# Power_USB.net
KiCad netlist of a schematic drawn in Altium Designer
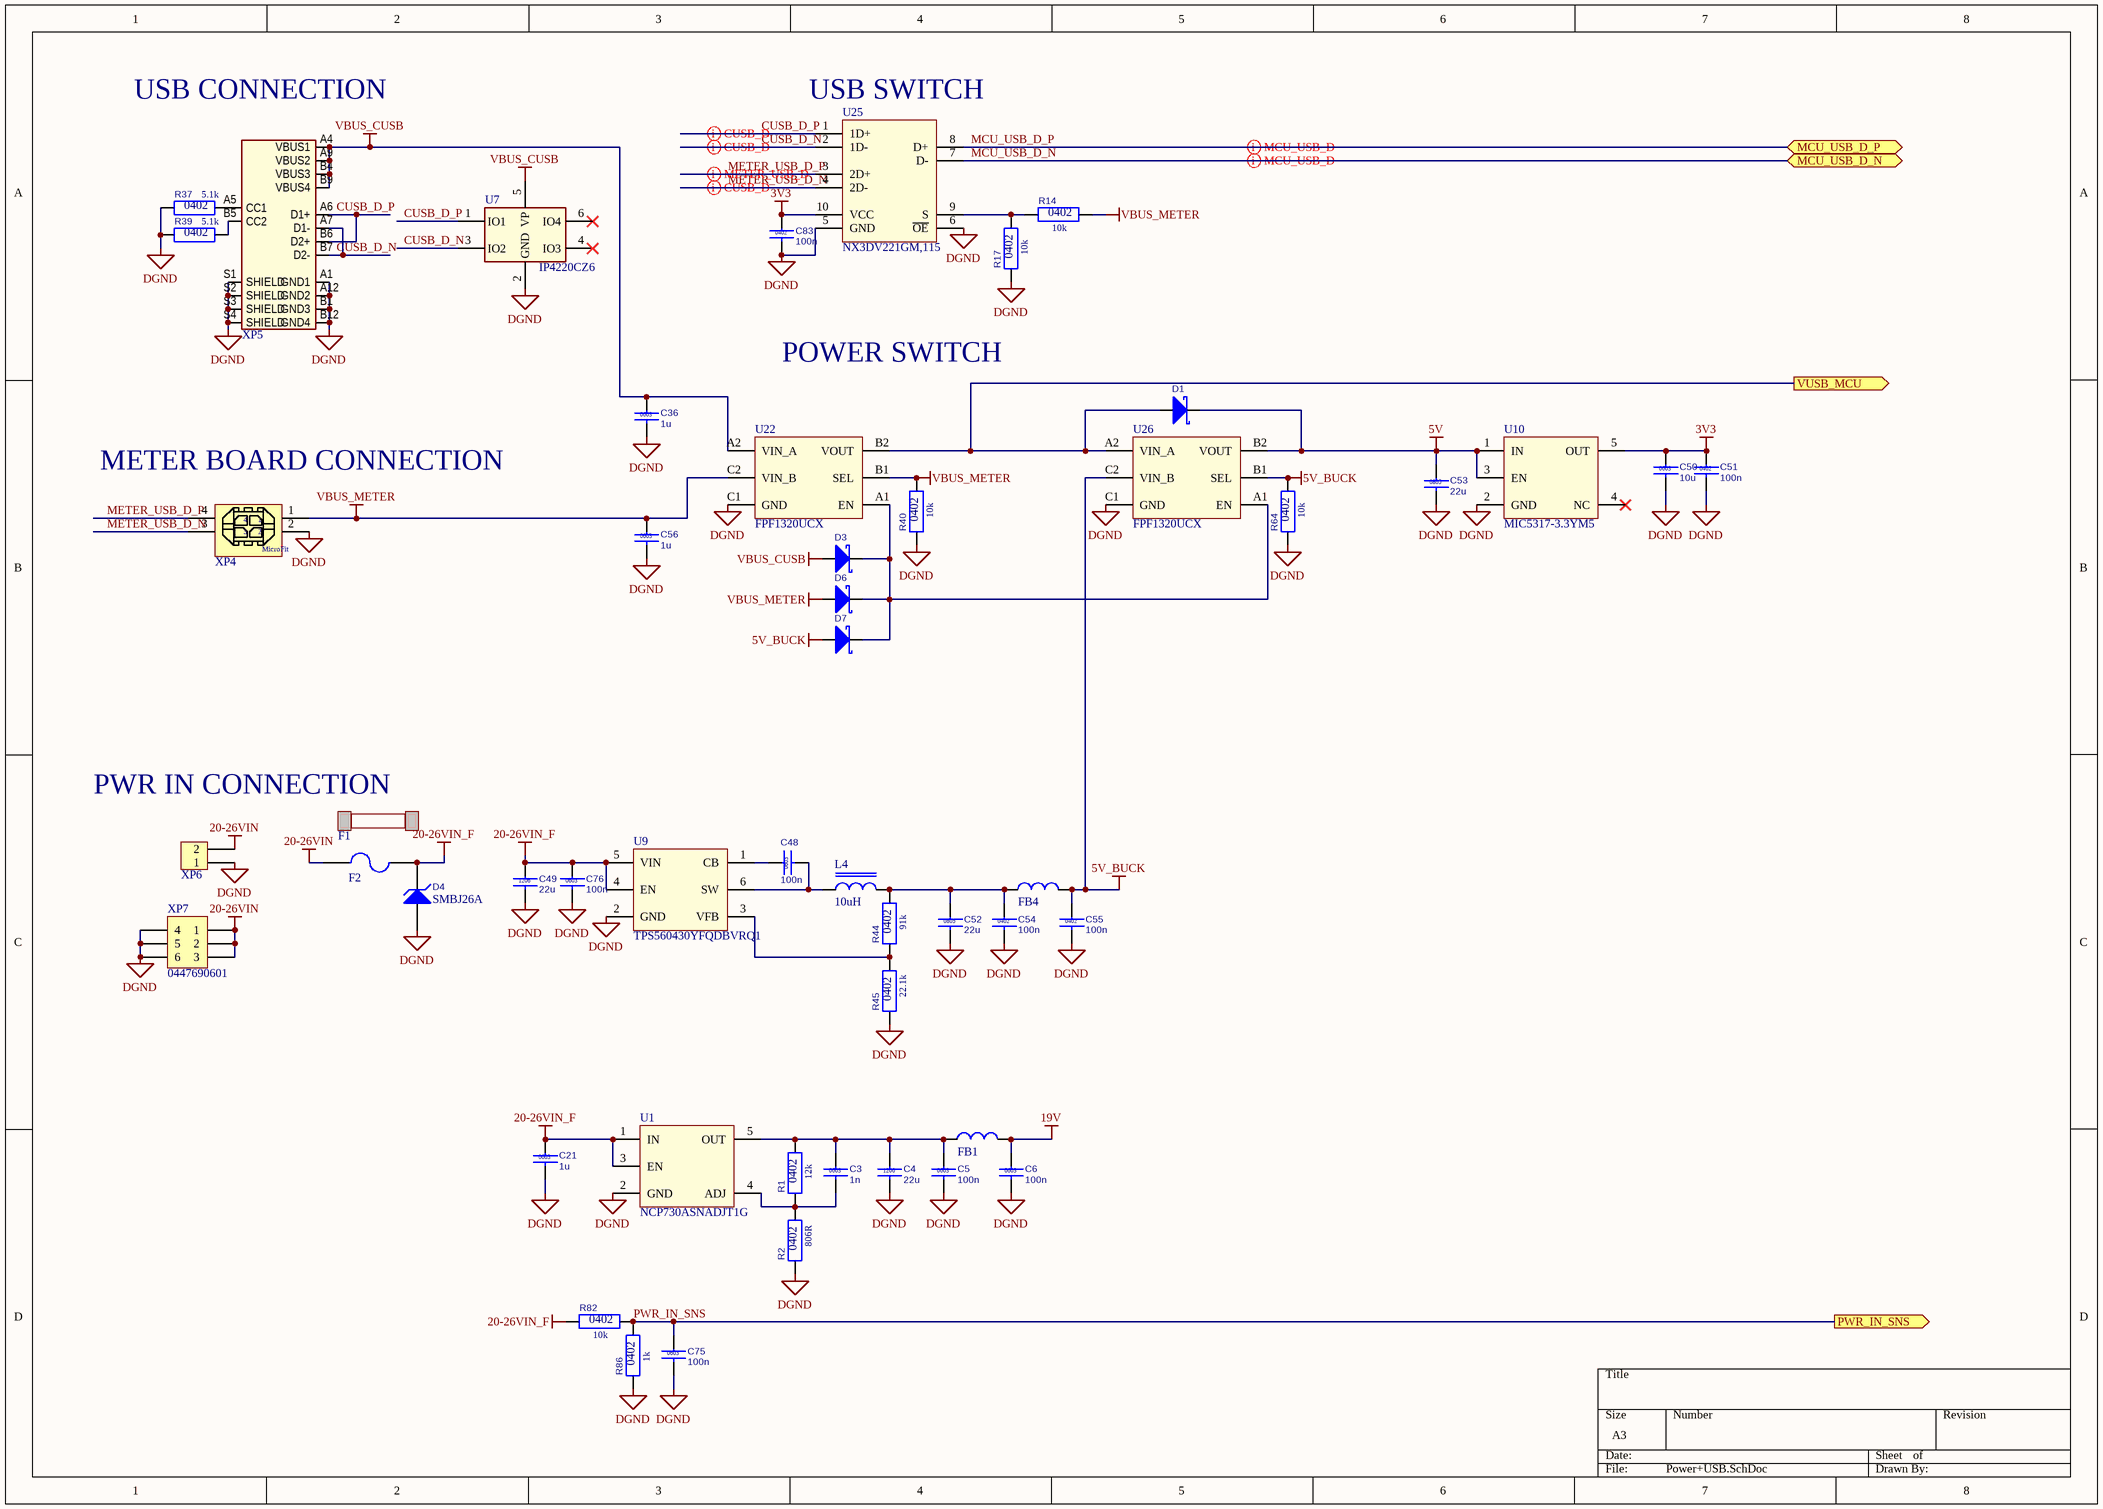
[diagram p0: Power+USB.SchDoc]

(export (version "E")
  (design (tool "Eeschema 10.0.6"))
  (components
    (comp (ref "C3")
      (value "1n")
      (footprint "CC0603M")
      (description "Chip ceramic capacitor")
      (fields
        (field (name "CASE") "0603")
        (field (name "PARTNUMBER") "CC0603K-X7R-50V-1N-M")
        (field (name "MANUFACTURER") "Yageo")
        (field (name "PUBLISHER") "alexey.savchenko")
      )
      (libsource (lib "AltiumLib") (part "Capacitor_nonpolar"))
    )
    (comp (ref "C4")
      (value "22u")
      (footprint "CC1206M")
      (description "Chip ceramic capacitor")
      (fields
        (field (name "CASE") "1206")
        (field (name "PARTNUMBER") "CC1206K-X5R-35V-22U-M")
        (field (name "MANUFACTURER") "TDK")
        (field (name "PUBLISHER") "alexey.savchenko")
      )
      (libsource (lib "AltiumLib") (part "Capacitor_nonpolar"))
    )
    (comp (ref "C5")
      (value "100n")
      (footprint "CC0603M")
      (description "Chip ceramic capacitor")
      (fields
        (field (name "CASE") "0603")
        (field (name "PARTNUMBER") "CC0603K-X7R-50V-100N-M")
        (field (name "MANUFACTURER") "Yageo")
        (field (name "PUBLISHER") "alexey.savchenko")
      )
      (libsource (lib "AltiumLib") (part "Capacitor_nonpolar"))
    )
    (comp (ref "C6")
      (value "100n")
      (footprint "CC0603M")
      (description "Chip ceramic capacitor")
      (fields
        (field (name "CASE") "0603")
        (field (name "PARTNUMBER") "CC0603K-X7R-50V-100N-M")
        (field (name "MANUFACTURER") "Yageo")
        (field (name "PUBLISHER") "alexey.savchenko")
      )
      (libsource (lib "AltiumLib") (part "Capacitor_nonpolar"))
    )
    (comp (ref "C21")
      (value "1u")
      (footprint "CC0603M")
      (description "Chip ceramic capacitor")
      (fields
        (field (name "CASE") "0603")
        (field (name "PARTNUMBER") "CC0603K-X5R-50V-1U-M")
        (field (name "MANUFACTURER") "Samsung")
        (field (name "PUBLISHER") "alexey.savchenko")
      )
      (libsource (lib "AltiumLib") (part "Capacitor_nonpolar"))
    )
    (comp (ref "C36")
      (value "1u")
      (footprint "CC0603M")
      (description "Chip ceramic capacitor")
      (fields
        (field (name "CASE") "0603")
        (field (name "PARTNUMBER") "CC0603K-X7R-10V-1U-M")
        (field (name "MANUFACTURER") "Samsung")
        (field (name "PUBLISHER") "alexey.savchenko")
      )
      (libsource (lib "AltiumLib") (part "Capacitor_nonpolar"))
    )
    (comp (ref "C48")
      (value "100n")
      (footprint "CC0603M")
      (description "Chip ceramic capacitor")
      (fields
        (field (name "CASE") "0603")
        (field (name "PARTNUMBER") "CC0603K-X7R-50V-100N-M")
        (field (name "MANUFACTURER") "Yageo")
        (field (name "PUBLISHER") "alexey.savchenko")
      )
      (libsource (lib "AltiumLib") (part "Capacitor_nonpolar"))
    )
    (comp (ref "C49")
      (value "22u")
      (footprint "CC1206M")
      (description "Chip ceramic capacitor")
      (fields
        (field (name "CASE") "1206")
        (field (name "PARTNUMBER") "CC1206K-X5R-35V-22U-M")
        (field (name "MANUFACTURER") "TDK")
        (field (name "PUBLISHER") "alexey.savchenko")
      )
      (libsource (lib "AltiumLib") (part "Capacitor_nonpolar"))
    )
    (comp (ref "C50")
      (value "10u")
      (footprint "CC0603M")
      (description "Chip ceramic capacitor")
      (fields
        (field (name "CASE") "0603")
        (field (name "PARTNUMBER") "CC0603K-X5R-10V-10U-M")
        (field (name "MANUFACTURER") "Murata")
        (field (name "PUBLISHER") "alexey.savchenko")
      )
      (libsource (lib "AltiumLib") (part "Capacitor_nonpolar"))
    )
    (comp (ref "C51")
      (value "100n")
      (footprint "CC0402M")
      (description "Chip ceramic capacitor")
      (fields
        (field (name "CASE") "0402")
        (field (name "PARTNUMBER") "CC0402K-X7R-25V-100N-M")
        (field (name "MANUFACTURER") "Murata")
        (field (name "PUBLISHER") "alexey.savchenko")
      )
      (libsource (lib "AltiumLib") (part "Capacitor_nonpolar"))
    )
    (comp (ref "C52")
      (value "22u")
      (footprint "CC0805M")
      (description "Chip ceramic capacitor")
      (fields
        (field (name "CASE") "0805")
        (field (name "PARTNUMBER") "CC0805K-X5R-10V-22U-M")
        (field (name "MANUFACTURER") "Samsung")
        (field (name "PUBLISHER") "alexey.savchenko")
      )
      (libsource (lib "AltiumLib") (part "Capacitor_nonpolar"))
    )
    (comp (ref "C53")
      (value "22u")
      (footprint "CC0805M")
      (description "Chip ceramic capacitor")
      (fields
        (field (name "CASE") "0805")
        (field (name "PARTNUMBER") "CC0805K-X5R-10V-22U-M")
        (field (name "MANUFACTURER") "Samsung")
        (field (name "PUBLISHER") "alexey.savchenko")
      )
      (libsource (lib "AltiumLib") (part "Capacitor_nonpolar"))
    )
    (comp (ref "C54")
      (value "100n")
      (footprint "CC0402M")
      (description "Chip ceramic capacitor")
      (fields
        (field (name "CASE") "0402")
        (field (name "PARTNUMBER") "CC0402K-X7R-25V-100N-M")
        (field (name "MANUFACTURER") "Murata")
        (field (name "PUBLISHER") "alexey.savchenko")
      )
      (libsource (lib "AltiumLib") (part "Capacitor_nonpolar"))
    )
    (comp (ref "C55")
      (value "100n")
      (footprint "CC0402M")
      (description "Chip ceramic capacitor")
      (fields
        (field (name "CASE") "0402")
        (field (name "PARTNUMBER") "CC0402K-X7R-25V-100N-M")
        (field (name "MANUFACTURER") "Murata")
        (field (name "PUBLISHER") "alexey.savchenko")
      )
      (libsource (lib "AltiumLib") (part "Capacitor_nonpolar"))
    )
    (comp (ref "C56")
      (value "1u")
      (footprint "CC0603M")
      (description "Chip ceramic capacitor")
      (fields
        (field (name "CASE") "0603")
        (field (name "PARTNUMBER") "CC0603K-X7R-10V-1U-M")
        (field (name "MANUFACTURER") "Samsung")
        (field (name "PUBLISHER") "alexey.savchenko")
      )
      (libsource (lib "AltiumLib") (part "Capacitor_nonpolar"))
    )
    (comp (ref "C75")
      (value "100n")
      (footprint "CC0603M")
      (description "Chip ceramic capacitor")
      (fields
        (field (name "CASE") "0603")
        (field (name "PARTNUMBER") "CC0603K-X7R-50V-100N-M")
        (field (name "MANUFACTURER") "Yageo")
        (field (name "PUBLISHER") "alexey.savchenko")
      )
      (libsource (lib "AltiumLib") (part "Capacitor_nonpolar"))
    )
    (comp (ref "C76")
      (value "100n")
      (footprint "CC0603M")
      (description "Chip ceramic capacitor")
      (fields
        (field (name "CASE") "0603")
        (field (name "PARTNUMBER") "CC0603K-X7R-50V-100N-M")
        (field (name "MANUFACTURER") "Yageo")
        (field (name "PUBLISHER") "alexey.savchenko")
      )
      (libsource (lib "AltiumLib") (part "Capacitor_nonpolar"))
    )
    (comp (ref "C83")
      (value "100n")
      (footprint "CC0402M")
      (description "Chip ceramic capacitor")
      (fields
        (field (name "CASE") "0402")
        (field (name "PARTNUMBER") "CC0402K-X7R-25V-100N-M")
        (field (name "MANUFACTURER") "Murata")
        (field (name "PUBLISHER") "alexey.savchenko")
      )
      (libsource (lib "AltiumLib") (part "Capacitor_nonpolar"))
    )
    (comp (ref "D1")
      (value "BAT54HT1G")
      (footprint "SOD323")
      (description "DIODE SCHOTTKY 30V 200MA SOD323")
      (fields (field (name "MANUFACTURER") "ON Semiconductor") (field (name "PUBLISHER") "alexey.savchenko"))
      (libsource (lib "AltiumLib") (part "SCHOTTKY_DIODE"))
    )
    (comp (ref "D3")
      (value "BAT54HT1G")
      (footprint "SOD323")
      (description "DIODE SCHOTTKY 30V 200MA SOD323")
      (fields (field (name "MANUFACTURER") "ON Semiconductor") (field (name "PUBLISHER") "alexey.savchenko"))
      (libsource (lib "AltiumLib") (part "SCHOTTKY_DIODE"))
    )
    (comp (ref "D4")
      (value "SMBJ26A")
      (footprint "SMB_UNI")
      (description "TVS DIODE Unidirectional 26V DO214AA")
      (fields (field (name "MANUFACTURER") "Littelfuse Inc.") (field (name "PUBLISHER") "alexey.savchenko"))
      (libsource (lib "AltiumLib") (part "TVS-UNI"))
    )
    (comp (ref "D6")
      (value "BAT54HT1G")
      (footprint "SOD323")
      (description "DIODE SCHOTTKY 30V 200MA SOD323")
      (fields (field (name "MANUFACTURER") "ON Semiconductor") (field (name "PUBLISHER") "alexey.savchenko"))
      (libsource (lib "AltiumLib") (part "SCHOTTKY_DIODE"))
    )
    (comp (ref "D7")
      (value "BAT54HT1G")
      (footprint "SOD323")
      (description "DIODE SCHOTTKY 30V 200MA SOD323")
      (fields (field (name "MANUFACTURER") "ON Semiconductor") (field (name "PUBLISHER") "alexey.savchenko"))
      (libsource (lib "AltiumLib") (part "SCHOTTKY_DIODE"))
    )
    (comp (ref "F1")
      (value "0217015.MXP")
      (description "15A 250V AC DC Fuse Cartridge, Glass Holder 5mm x 20mm")
      (fields (field (name "MANUFACTURER") "Littlefuse") (field (name "PUBLISHER") "alexey.savchenko"))
      (libsource (lib "AltiumLib") (part "FUSE_GLASS"))
    )
    (comp (ref "F2")
      (value "696108003002")
      (footprint "696108003002")
      (description "FUSEHOLDER BLOCKS - PCB - CLIP C")
      (fields (field (name "MANUFACTURER") "Würth Elektronik") (field (name "PUBLISHER") "alexey.savchenko"))
      (libsource (lib "AltiumLib") (part "FUSE_HOLDER"))
    )
    (comp (ref "FB1")
      (value "BLM18HG102SN1D")
      (footprint "FB0603M")
      (description "FERRITE BEAD 1 KOHM 0603 1LN")
      (fields (field (name "MANUFACTURER") "Murata") (field (name "PUBLISHER") "alexey.savchenko"))
      (libsource (lib "AltiumLib") (part "FerriteBead"))
    )
    (comp (ref "FB4")
      (value "BLM21SP601SH1D")
      (footprint "FB0805M")
      (description "600 Ohms @ 100MHz 1 Power Line Ferrite Bead 0805 (2012 Metric) 2.3A")
      (fields (field (name "MANUFACTURER") "Murata") (field (name "PUBLISHER") "alexey.savchenko"))
      (libsource (lib "AltiumLib") (part "FerriteBead"))
    )
    (comp (ref "L4")
      (value "10uH")
      (footprint "0518CDMCCDS")
      (description "10µH Shielded Molded Inductor 2.3A 155mOhm Max Nonstandard")
      (fields
        (field (name "PARTNUMBER") "0518CDMCCDS-100MC")
        (field (name "MANUFACTURER") "Sumida")
        (field (name "PUBLISHER") "alexey.savchenko")
      )
      (libsource (lib "AltiumLib") (part "Inductor"))
    )
    (comp (ref "R1")
      (value "12k")
      (footprint "RC0402M")
      (description "Chip resistor")
      (fields
        (field (name "CASE") "0402")
        (field (name "PARTNUMBER") "RC0402F-12K-M")
        (field (name "MANUFACTURER") "Yageo")
        (field (name "PUBLISHER") "alexey.savchenko")
      )
      (libsource (lib "AltiumLib") (part "Resistor"))
    )
    (comp (ref "R2")
      (value "806R")
      (footprint "RC0402M")
      (description "Chip resistor")
      (fields
        (field (name "CASE") "0402")
        (field (name "PARTNUMBER") "RC0402F-806R-M")
        (field (name "MANUFACTURER") "Yageo")
        (field (name "PUBLISHER") "alexey.savchenko")
      )
      (libsource (lib "AltiumLib") (part "Resistor"))
    )
    (comp (ref "R14")
      (value "10k")
      (footprint "RC0402M")
      (description "Chip resistor")
      (fields
        (field (name "CASE") "0402")
        (field (name "PARTNUMBER") "RC0402F-10K-M")
        (field (name "MANUFACTURER") "Yageo")
        (field (name "PUBLISHER") "alexey.savchenko")
      )
      (libsource (lib "AltiumLib") (part "Resistor"))
    )
    (comp (ref "R17")
      (value "10k")
      (footprint "RC0402M")
      (description "Chip resistor")
      (fields
        (field (name "CASE") "0402")
        (field (name "PARTNUMBER") "RC0402F-10K-M")
        (field (name "MANUFACTURER") "Yageo")
        (field (name "PUBLISHER") "alexey.savchenko")
      )
      (libsource (lib "AltiumLib") (part "Resistor"))
    )
    (comp (ref "R37")
      (value "5.1k")
      (footprint "RC0402M")
      (description "Chip resistor")
      (fields
        (field (name "CASE") "0402")
        (field (name "PARTNUMBER") "RC0402F-5K1-M")
        (field (name "POWER") "0.063W")
        (field (name "PUBLISHER") "alexey.savchenko")
      )
      (libsource (lib "AltiumLib") (part "Resistor"))
    )
    (comp (ref "R39")
      (value "5.1k")
      (footprint "RC0402M")
      (description "Chip resistor")
      (fields
        (field (name "CASE") "0402")
        (field (name "PARTNUMBER") "RC0402F-5K1-M")
        (field (name "POWER") "0.063W")
        (field (name "PUBLISHER") "alexey.savchenko")
      )
      (libsource (lib "AltiumLib") (part "Resistor"))
    )
    (comp (ref "R40")
      (value "10k")
      (footprint "RC0402M")
      (description "Chip resistor")
      (fields
        (field (name "CASE") "0402")
        (field (name "PARTNUMBER") "RC0402F-10K-M")
        (field (name "MANUFACTURER") "Yageo")
        (field (name "PUBLISHER") "alexey.savchenko")
      )
      (libsource (lib "AltiumLib") (part "Resistor"))
    )
    (comp (ref "R44")
      (value "91k")
      (footprint "RC0402M")
      (description "Chip resistor")
      (fields
        (field (name "CASE") "0402")
        (field (name "PARTNUMBER") "RC0402F-91K-M")
        (field (name "POWER") "0.063W")
        (field (name "PUBLISHER") "alexey.savchenko")
      )
      (libsource (lib "AltiumLib") (part "Resistor"))
    )
    (comp (ref "R45")
      (value "22.1k")
      (footprint "RC0402M")
      (description "Chip resistor")
      (fields
        (field (name "CASE") "0402")
        (field (name "PARTNUMBER") "RC0402F-22K1-M")
        (field (name "POWER") "0.063W")
        (field (name "PUBLISHER") "alexey.savchenko")
      )
      (libsource (lib "AltiumLib") (part "Resistor"))
    )
    (comp (ref "R64")
      (value "10k")
      (footprint "RC0402M")
      (description "Chip resistor")
      (fields
        (field (name "CASE") "0402")
        (field (name "PARTNUMBER") "RC0402F-10K-M")
        (field (name "MANUFACTURER") "Yageo")
        (field (name "PUBLISHER") "alexey.savchenko")
      )
      (libsource (lib "AltiumLib") (part "Resistor"))
    )
    (comp (ref "R82")
      (value "10k")
      (footprint "RC0402M")
      (description "Chip resistor")
      (fields
        (field (name "CASE") "0402")
        (field (name "PARTNUMBER") "RC0402F-10K-M")
        (field (name "MANUFACTURER") "Yageo")
        (field (name "PUBLISHER") "alexey.savchenko")
      )
      (libsource (lib "AltiumLib") (part "Resistor"))
    )
    (comp (ref "R86")
      (value "1k")
      (footprint "RC0402M")
      (description "Chip resistor")
      (fields
        (field (name "CASE") "0402")
        (field (name "PARTNUMBER") "RC0402F-1K-M")
        (field (name "MANUFACTURER") "Yageo")
        (field (name "PUBLISHER") "alexey.savchenko")
      )
      (libsource (lib "AltiumLib") (part "Resistor"))
    )
    (comp (ref "U1")
      (value "NCP730ASNADJT1G")
      (footprint "TSOP-5")
      (description "NCP730 TSOP-5 ADJ")
      (fields (field (name "MANUFACTURER") "ON Semiconductor") (field (name "PUBLISHER") "alexey.savchenko"))
      (libsource (lib "AltiumLib") (part "NCP730ASNADJT1G"))
    )
    (comp (ref "U7")
      (value "IP4220CZ6")
      (footprint "TSOP-6")
      (description "TVS DIODE 5.5V 6TSOP")
      (fields (field (name "MANUFACTURER") "Nexperia") (field (name "PUBLISHER") "alexey.savchenko"))
      (libsource (lib "AltiumLib") (part "IP4220CZ6"))
    )
    (comp (ref "U9")
      (value "TPS560430YFQDBVRQ1")
      (footprint "SOT23-6")
      (description "Buck Switching Regulator IC Positive Adjustable 1V 1 Output 600mA SOT-23-6")
      (fields (field (name "MANUFACTURER") "TI") (field (name "PUBLISHER") "alexey.savchenko"))
      (libsource (lib "AltiumLib") (part "TPS560430Y"))
    )
    (comp (ref "U10")
      (value "MIC5317-3.3YM5")
      (footprint "SOT23-5")
      (description "Linear Voltage Regulator IC 1 Output 150mA SOT-23-5")
      (fields (field (name "MANUFACTURER") "Microchip") (field (name "PUBLISHER") "alexey.savchenko"))
      (libsource (lib "AltiumLib") (part "MIC5317"))
    )
    (comp (ref "U22")
      (value "FPF1320UCX")
      (footprint "WLCSP-6")
      (description "Power Switch/Driver 2:1 P-Channel 1.5A 6-WLCSP (0.96x1.66)")
      (fields (field (name "MANUFACTURER") "ON Semiconductor") (field (name "PUBLISHER") "alexey.savchenko"))
      (libsource (lib "AltiumLib") (part "FPF1320UCX"))
    )
    (comp (ref "U25")
      (value "NX3DV221GM,115")
      (footprint "XQFN-10(SOT1049-3)")
      (description "IC USB 2.0 SWITCH HS 10XQFN")
      (fields (field (name "MANUFACTURER") "NXP") (field (name "PUBLISHER") "alexey.savchenko"))
      (libsource (lib "AltiumLib") (part "NX3DV221GM"))
    )
    (comp (ref "U26")
      (value "FPF1320UCX")
      (footprint "WLCSP-6")
      (description "Power Switch/Driver 2:1 P-Channel 1.5A 6-WLCSP (0.96x1.66)")
      (fields (field (name "MANUFACTURER") "ON Semiconductor") (field (name "PUBLISHER") "alexey.savchenko"))
      (libsource (lib "AltiumLib") (part "FPF1320UCX"))
    )
    (comp (ref "XP4")
      (value "0447690401")
      (footprint "0447690401")
      (fields (field (name "MANUFACTURER") "Molex") (field (name "PUBLISHER") "alexey.savchenko"))
      (libsource (lib "AltiumLib") (part "MicroFit-2x2"))
    )
    (comp (ref "XP5")
      (value "KUSBX-SL-CS1N14-B")
      (footprint "KUSBX-SL-CS1N14-B")
      (description "CONN USB TYPE-C TH UPRIGHT FLAG")
      (fields (field (name "MANUFACTURER") "Kycon") (field (name "PUBLISHER") "alexey.savchenko"))
      (libsource (lib "AltiumLib") (part "KUSBX-SL-CS1N14-B"))
    )
    (comp (ref "XP6")
      (value "TBH-2x5.08P-RA-GN")
      (footprint "TBH-2x5.08P-RA-GN")
      (description "TERM BLOCK HDR 2POS 90DEG 5.08MM, Green")
      (fields (field (name "MANUFACTURER") "Phoenix Contact") (field (name "PUBLISHER") "alexey.savchenko"))
      (libsource (lib "AltiumLib") (part "TBH-2x"))
    )
    (comp (ref "XP7")
      (value "0447690601")
      (footprint "0447690601")
      (fields (field (name "MANUFACTURER") "Molex") (field (name "PUBLISHER") "alexey.savchenko"))
      (libsource (lib "AltiumLib") (part "MicroFit-2x3"))
    )
  )
  (nets
    (net (code "1") (name "/CUSB_D_N") (class "Default")
      (node (ref "U25") (pin "2") (pinfunction "1D-_2") (pintype "passive"))
      (node (ref "U7") (pin "3") (pinfunction "IO2_3") (pintype "passive"))
      (node (ref "XP5") (pin "A7") (pinfunction "D1-_A7") (pintype "passive"))
      (node (ref "XP5") (pin "B7") (pinfunction "D2-_B7") (pintype "passive"))
    )
    (net (code "2") (name "/CUSB_D_P") (class "Default")
      (node (ref "U25") (pin "1") (pinfunction "1D+_1") (pintype "passive"))
      (node (ref "U7") (pin "1") (pinfunction "IO1_1") (pintype "passive"))
      (node (ref "XP5") (pin "A6") (pinfunction "D1+_A6") (pintype "passive"))
      (node (ref "XP5") (pin "B6") (pinfunction "D2+_B6") (pintype "passive"))
    )
    (net (code "3") (name "/MCU_USB_D_N") (class "Default")
      (node (ref "U25") (pin "7") (pinfunction "D-_7") (pintype "passive"))
    )
    (net (code "4") (name "/MCU_USB_D_P") (class "Default")
      (node (ref "U25") (pin "8") (pinfunction "D+_8") (pintype "passive"))
    )
    (net (code "5") (name "/METER_USB_D_N") (class "Default")
      (node (ref "U25") (pin "4") (pinfunction "2D-_4") (pintype "passive"))
      (node (ref "XP4") (pin "3") (pinfunction "3_3") (pintype "passive"))
    )
    (net (code "6") (name "/METER_USB_D_P") (class "Default")
      (node (ref "U25") (pin "3") (pinfunction "2D+_3") (pintype "passive"))
      (node (ref "XP4") (pin "4") (pinfunction "4_4") (pintype "passive"))
    )
    (net (code "7") (name "/PWR_IN_SNS") (class "Default")
      (node (ref "C75") (pin "1") (pinfunction "1_1") (pintype "passive"))
      (node (ref "R82") (pin "2") (pinfunction "2_2") (pintype "passive"))
      (node (ref "R86") (pin "2") (pinfunction "2_2") (pintype "passive"))
    )
    (net (code "8") (name "/VUSB_MCU") (class "Default")
      (node (ref "D1") (pin "2") (pinfunction "A_2") (pintype "passive"))
      (node (ref "U22") (pin "B2") (pinfunction "VOUT_B2") (pintype "passive"))
      (node (ref "U26") (pin "A2") (pinfunction "VIN_A_A2") (pintype "passive"))
    )
    (net (code "9") (name "3V3") (class "Default")
      (node (ref "C50") (pin "1") (pinfunction "1_1") (pintype "passive"))
      (node (ref "C51") (pin "1") (pinfunction "1_1") (pintype "passive"))
      (node (ref "C83") (pin "1") (pinfunction "1_1") (pintype "passive"))
      (node (ref "U10") (pin "5") (pinfunction "OUT_5") (pintype "passive"))
      (node (ref "U25") (pin "10") (pinfunction "VCC_10") (pintype "passive"))
    )
    (net (code "10") (name "5V") (class "Default")
      (node (ref "C53") (pin "1") (pinfunction "1_1") (pintype "passive"))
      (node (ref "D1") (pin "1") (pinfunction "K_1") (pintype "passive"))
      (node (ref "U10") (pin "1") (pinfunction "IN_1") (pintype "passive"))
      (node (ref "U10") (pin "3") (pinfunction "EN_3") (pintype "passive"))
      (node (ref "U26") (pin "B2") (pinfunction "VOUT_B2") (pintype "passive"))
    )
    (net (code "11") (name "5V_BUCK") (class "Default")
      (node (ref "C55") (pin "1") (pinfunction "1_1") (pintype "passive"))
      (node (ref "D7") (pin "2") (pinfunction "A_2") (pintype "passive"))
      (node (ref "FB4") (pin "2") (pinfunction "2_2") (pintype "passive"))
      (node (ref "R64") (pin "2") (pinfunction "2_2") (pintype "passive"))
      (node (ref "U26") (pin "B1") (pinfunction "SEL_B1") (pintype "passive"))
      (node (ref "U26") (pin "C2") (pinfunction "VIN_B_C2") (pintype "passive"))
    )
    (net (code "12") (name "19V") (class "Default")
      (node (ref "C6") (pin "1") (pinfunction "1_1") (pintype "passive"))
      (node (ref "FB1") (pin "2") (pinfunction "2_2") (pintype "passive"))
    )
    (net (code "13") (name "20-26VIN") (class "Default")
      (node (ref "F2") (pin "1") (pinfunction "1_1") (pintype "passive"))
      (node (ref "XP6") (pin "2") (pinfunction "2_2") (pintype "passive"))
      (node (ref "XP7") (pin "1") (pinfunction "1_1") (pintype "passive"))
      (node (ref "XP7") (pin "2") (pinfunction "2_2") (pintype "passive"))
      (node (ref "XP7") (pin "3") (pinfunction "3_3") (pintype "passive"))
    )
    (net (code "14") (name "20-26VIN_F") (class "Default")
      (node (ref "C21") (pin "1") (pinfunction "1_1") (pintype "passive"))
      (node (ref "C49") (pin "1") (pinfunction "1_1") (pintype "passive"))
      (node (ref "C76") (pin "1") (pinfunction "1_1") (pintype "passive"))
      (node (ref "D4") (pin "1") (pinfunction "K_1") (pintype "passive"))
      (node (ref "F2") (pin "2") (pinfunction "2_2") (pintype "passive"))
      (node (ref "R82") (pin "1") (pinfunction "1_1") (pintype "passive"))
      (node (ref "U1") (pin "1") (pinfunction "IN_1") (pintype "passive"))
      (node (ref "U1") (pin "3") (pinfunction "EN_3") (pintype "passive"))
      (node (ref "U9") (pin "4") (pinfunction "EN_4") (pintype "passive"))
      (node (ref "U9") (pin "5") (pinfunction "VIN_5") (pintype "passive"))
    )
    (net (code "15") (name "DGND") (class "Default")
      (node (ref "C21") (pin "2") (pinfunction "2_2") (pintype "passive"))
      (node (ref "C36") (pin "2") (pinfunction "2_2") (pintype "passive"))
      (node (ref "C4") (pin "2") (pinfunction "2_2") (pintype "passive"))
      (node (ref "C49") (pin "2") (pinfunction "2_2") (pintype "passive"))
      (node (ref "C5") (pin "2") (pinfunction "2_2") (pintype "passive"))
      (node (ref "C50") (pin "2") (pinfunction "2_2") (pintype "passive"))
      (node (ref "C51") (pin "2") (pinfunction "2_2") (pintype "passive"))
      (node (ref "C52") (pin "2") (pinfunction "2_2") (pintype "passive"))
      (node (ref "C53") (pin "2") (pinfunction "2_2") (pintype "passive"))
      (node (ref "C54") (pin "2") (pinfunction "2_2") (pintype "passive"))
      (node (ref "C55") (pin "2") (pinfunction "2_2") (pintype "passive"))
      (node (ref "C56") (pin "2") (pinfunction "2_2") (pintype "passive"))
      (node (ref "C6") (pin "2") (pinfunction "2_2") (pintype "passive"))
      (node (ref "C75") (pin "2") (pinfunction "2_2") (pintype "passive"))
      (node (ref "C76") (pin "2") (pinfunction "2_2") (pintype "passive"))
      (node (ref "C83") (pin "2") (pinfunction "2_2") (pintype "passive"))
      (node (ref "D4") (pin "2") (pinfunction "A_2") (pintype "passive"))
      (node (ref "R17") (pin "1") (pinfunction "1_1") (pintype "passive"))
      (node (ref "R2") (pin "1") (pinfunction "1_1") (pintype "passive"))
      (node (ref "R37") (pin "1") (pinfunction "1_1") (pintype "passive"))
      (node (ref "R39") (pin "1") (pinfunction "1_1") (pintype "passive"))
      (node (ref "R40") (pin "1") (pinfunction "1_1") (pintype "passive"))
      (node (ref "R45") (pin "1") (pinfunction "1_1") (pintype "passive"))
      (node (ref "R64") (pin "1") (pinfunction "1_1") (pintype "passive"))
      (node (ref "R86") (pin "1") (pinfunction "1_1") (pintype "passive"))
      (node (ref "U1") (pin "2") (pinfunction "GND_2") (pintype "passive"))
      (node (ref "U10") (pin "2") (pinfunction "GND_2") (pintype "passive"))
      (node (ref "U22") (pin "C1") (pinfunction "GND_C1") (pintype "passive"))
      (node (ref "U25") (pin "5") (pinfunction "GND_5") (pintype "passive"))
      (node (ref "U25") (pin "6") (pinfunction "~{OE}_6") (pintype "passive"))
      (node (ref "U26") (pin "C1") (pinfunction "GND_C1") (pintype "passive"))
      (node (ref "U7") (pin "2") (pinfunction "GND_2") (pintype "passive"))
      (node (ref "U9") (pin "2") (pinfunction "GND_2") (pintype "passive"))
      (node (ref "XP4") (pin "2") (pinfunction "2_2") (pintype "passive"))
      (node (ref "XP5") (pin "A1") (pinfunction "GND1_A1") (pintype "passive"))
      (node (ref "XP5") (pin "A12") (pinfunction "GND2_A12") (pintype "passive"))
      (node (ref "XP5") (pin "B1") (pinfunction "GND3_B1") (pintype "passive"))
      (node (ref "XP5") (pin "B12") (pinfunction "GND4_B12") (pintype "passive"))
      (node (ref "XP5") (pin "S1") (pinfunction "SHIELD_S1") (pintype "passive"))
      (node (ref "XP5") (pin "S2") (pinfunction "SHIELD_S2") (pintype "passive"))
      (node (ref "XP5") (pin "S3") (pinfunction "SHIELD_S3") (pintype "passive"))
      (node (ref "XP5") (pin "S4") (pinfunction "SHIELD_S4") (pintype "passive"))
      (node (ref "XP6") (pin "1") (pinfunction "1_1") (pintype "passive"))
      (node (ref "XP7") (pin "4") (pinfunction "4_4") (pintype "passive"))
      (node (ref "XP7") (pin "5") (pinfunction "5_5") (pintype "passive"))
      (node (ref "XP7") (pin "6") (pinfunction "6_6") (pintype "passive"))
    )
    (net (code "16") (name "Net-(C52-Pad1)") (class "Default")
      (node (ref "C52") (pin "1") (pinfunction "1_1") (pintype "passive"))
      (node (ref "C54") (pin "1") (pinfunction "1_1") (pintype "passive"))
      (node (ref "FB4") (pin "1") (pinfunction "1_1") (pintype "passive"))
      (node (ref "L4") (pin "2") (pinfunction "2_2") (pintype "passive"))
      (node (ref "R44") (pin "2") (pinfunction "2_2") (pintype "passive"))
    )
    (net (code "17") (name "Net-(D3-K)") (class "Default")
      (node (ref "D3") (pin "1") (pinfunction "K_1") (pintype "passive"))
      (node (ref "D6") (pin "1") (pinfunction "K_1") (pintype "passive"))
      (node (ref "D7") (pin "1") (pinfunction "K_1") (pintype "passive"))
      (node (ref "U22") (pin "A1") (pinfunction "EN_A1") (pintype "passive"))
      (node (ref "U26") (pin "A1") (pinfunction "EN_A1") (pintype "passive"))
    )
    (net (code "18") (name "Net-(U1-ADJ)") (class "Default")
      (node (ref "C3") (pin "2") (pinfunction "2_2") (pintype "passive"))
      (node (ref "R1") (pin "1") (pinfunction "1_1") (pintype "passive"))
      (node (ref "R2") (pin "2") (pinfunction "2_2") (pintype "passive"))
      (node (ref "U1") (pin "4") (pinfunction "ADJ_4") (pintype "passive"))
    )
    (net (code "19") (name "Net-(U1-OUT)") (class "Default")
      (node (ref "C3") (pin "1") (pinfunction "1_1") (pintype "passive"))
      (node (ref "C4") (pin "1") (pinfunction "1_1") (pintype "passive"))
      (node (ref "C5") (pin "1") (pinfunction "1_1") (pintype "passive"))
      (node (ref "FB1") (pin "1") (pinfunction "1_1") (pintype "passive"))
      (node (ref "R1") (pin "2") (pinfunction "2_2") (pintype "passive"))
      (node (ref "U1") (pin "5") (pinfunction "OUT_5") (pintype "passive"))
    )
    (net (code "20") (name "Net-(U9-CB)") (class "Default")
      (node (ref "C48") (pin "1") (pinfunction "1_1") (pintype "passive"))
      (node (ref "U9") (pin "1") (pinfunction "CB_1") (pintype "passive"))
    )
    (net (code "21") (name "Net-(U9-SW)") (class "Default")
      (node (ref "C48") (pin "2") (pinfunction "2_2") (pintype "passive"))
      (node (ref "L4") (pin "1") (pinfunction "1_1") (pintype "passive"))
      (node (ref "U9") (pin "6") (pinfunction "SW_6") (pintype "passive"))
    )
    (net (code "22") (name "Net-(U9-VFB)") (class "Default")
      (node (ref "R44") (pin "1") (pinfunction "1_1") (pintype "passive"))
      (node (ref "R45") (pin "2") (pinfunction "2_2") (pintype "passive"))
      (node (ref "U9") (pin "3") (pinfunction "VFB_3") (pintype "passive"))
    )
    (net (code "23") (name "Net-(U25-S)") (class "Default")
      (node (ref "R14") (pin "1") (pinfunction "1_1") (pintype "passive"))
      (node (ref "R17") (pin "2") (pinfunction "2_2") (pintype "passive"))
      (node (ref "U25") (pin "9") (pinfunction "S_9") (pintype "passive"))
    )
    (net (code "24") (name "Net-(XP5-CC1)") (class "Default")
      (node (ref "R37") (pin "2") (pinfunction "2_2") (pintype "passive"))
      (node (ref "XP5") (pin "A5") (pinfunction "CC1_A5") (pintype "passive"))
    )
    (net (code "25") (name "Net-(XP5-CC2)") (class "Default")
      (node (ref "R39") (pin "2") (pinfunction "2_2") (pintype "passive"))
      (node (ref "XP5") (pin "B5") (pinfunction "CC2_B5") (pintype "passive"))
    )
    (net (code "26") (name "VBUS_CUSB") (class "Default")
      (node (ref "C36") (pin "1") (pinfunction "1_1") (pintype "passive"))
      (node (ref "D3") (pin "2") (pinfunction "A_2") (pintype "passive"))
      (node (ref "U22") (pin "A2") (pinfunction "VIN_A_A2") (pintype "passive"))
      (node (ref "U7") (pin "5") (pinfunction "VP_5") (pintype "passive"))
      (node (ref "XP5") (pin "A4") (pinfunction "VBUS1_A4") (pintype "passive"))
      (node (ref "XP5") (pin "A9") (pinfunction "VBUS2_A9") (pintype "passive"))
      (node (ref "XP5") (pin "B4") (pinfunction "VBUS3_B4") (pintype "passive"))
      (node (ref "XP5") (pin "B9") (pinfunction "VBUS4_B9") (pintype "passive"))
    )
    (net (code "27") (name "VBUS_METER") (class "Default")
      (node (ref "C56") (pin "1") (pinfunction "1_1") (pintype "passive"))
      (node (ref "D6") (pin "2") (pinfunction "A_2") (pintype "passive"))
      (node (ref "R14") (pin "2") (pinfunction "2_2") (pintype "passive"))
      (node (ref "R40") (pin "2") (pinfunction "2_2") (pintype "passive"))
      (node (ref "U22") (pin "B1") (pinfunction "SEL_B1") (pintype "passive"))
      (node (ref "U22") (pin "C2") (pinfunction "VIN_B_C2") (pintype "passive"))
      (node (ref "XP4") (pin "1") (pinfunction "1_1") (pintype "passive"))
    )
    (net (code "28") (name "unconnected-(U7-IO3-Pad4)") (class "Default")
      (node (ref "U7") (pin "4") (pinfunction "IO3_4") (pintype "passive+no_connect"))
    )
    (net (code "29") (name "unconnected-(U7-IO4-Pad6)") (class "Default")
      (node (ref "U7") (pin "6") (pinfunction "IO4_6") (pintype "passive+no_connect"))
    )
    (net (code "30") (name "unconnected-(U10-NC-Pad4)") (class "Default")
      (node (ref "U10") (pin "4") (pinfunction "NC_4") (pintype "passive+no_connect"))
    )
  )
)
